# CHR_ver2.net
KiCad netlist of a schematic drawn in EAGLE
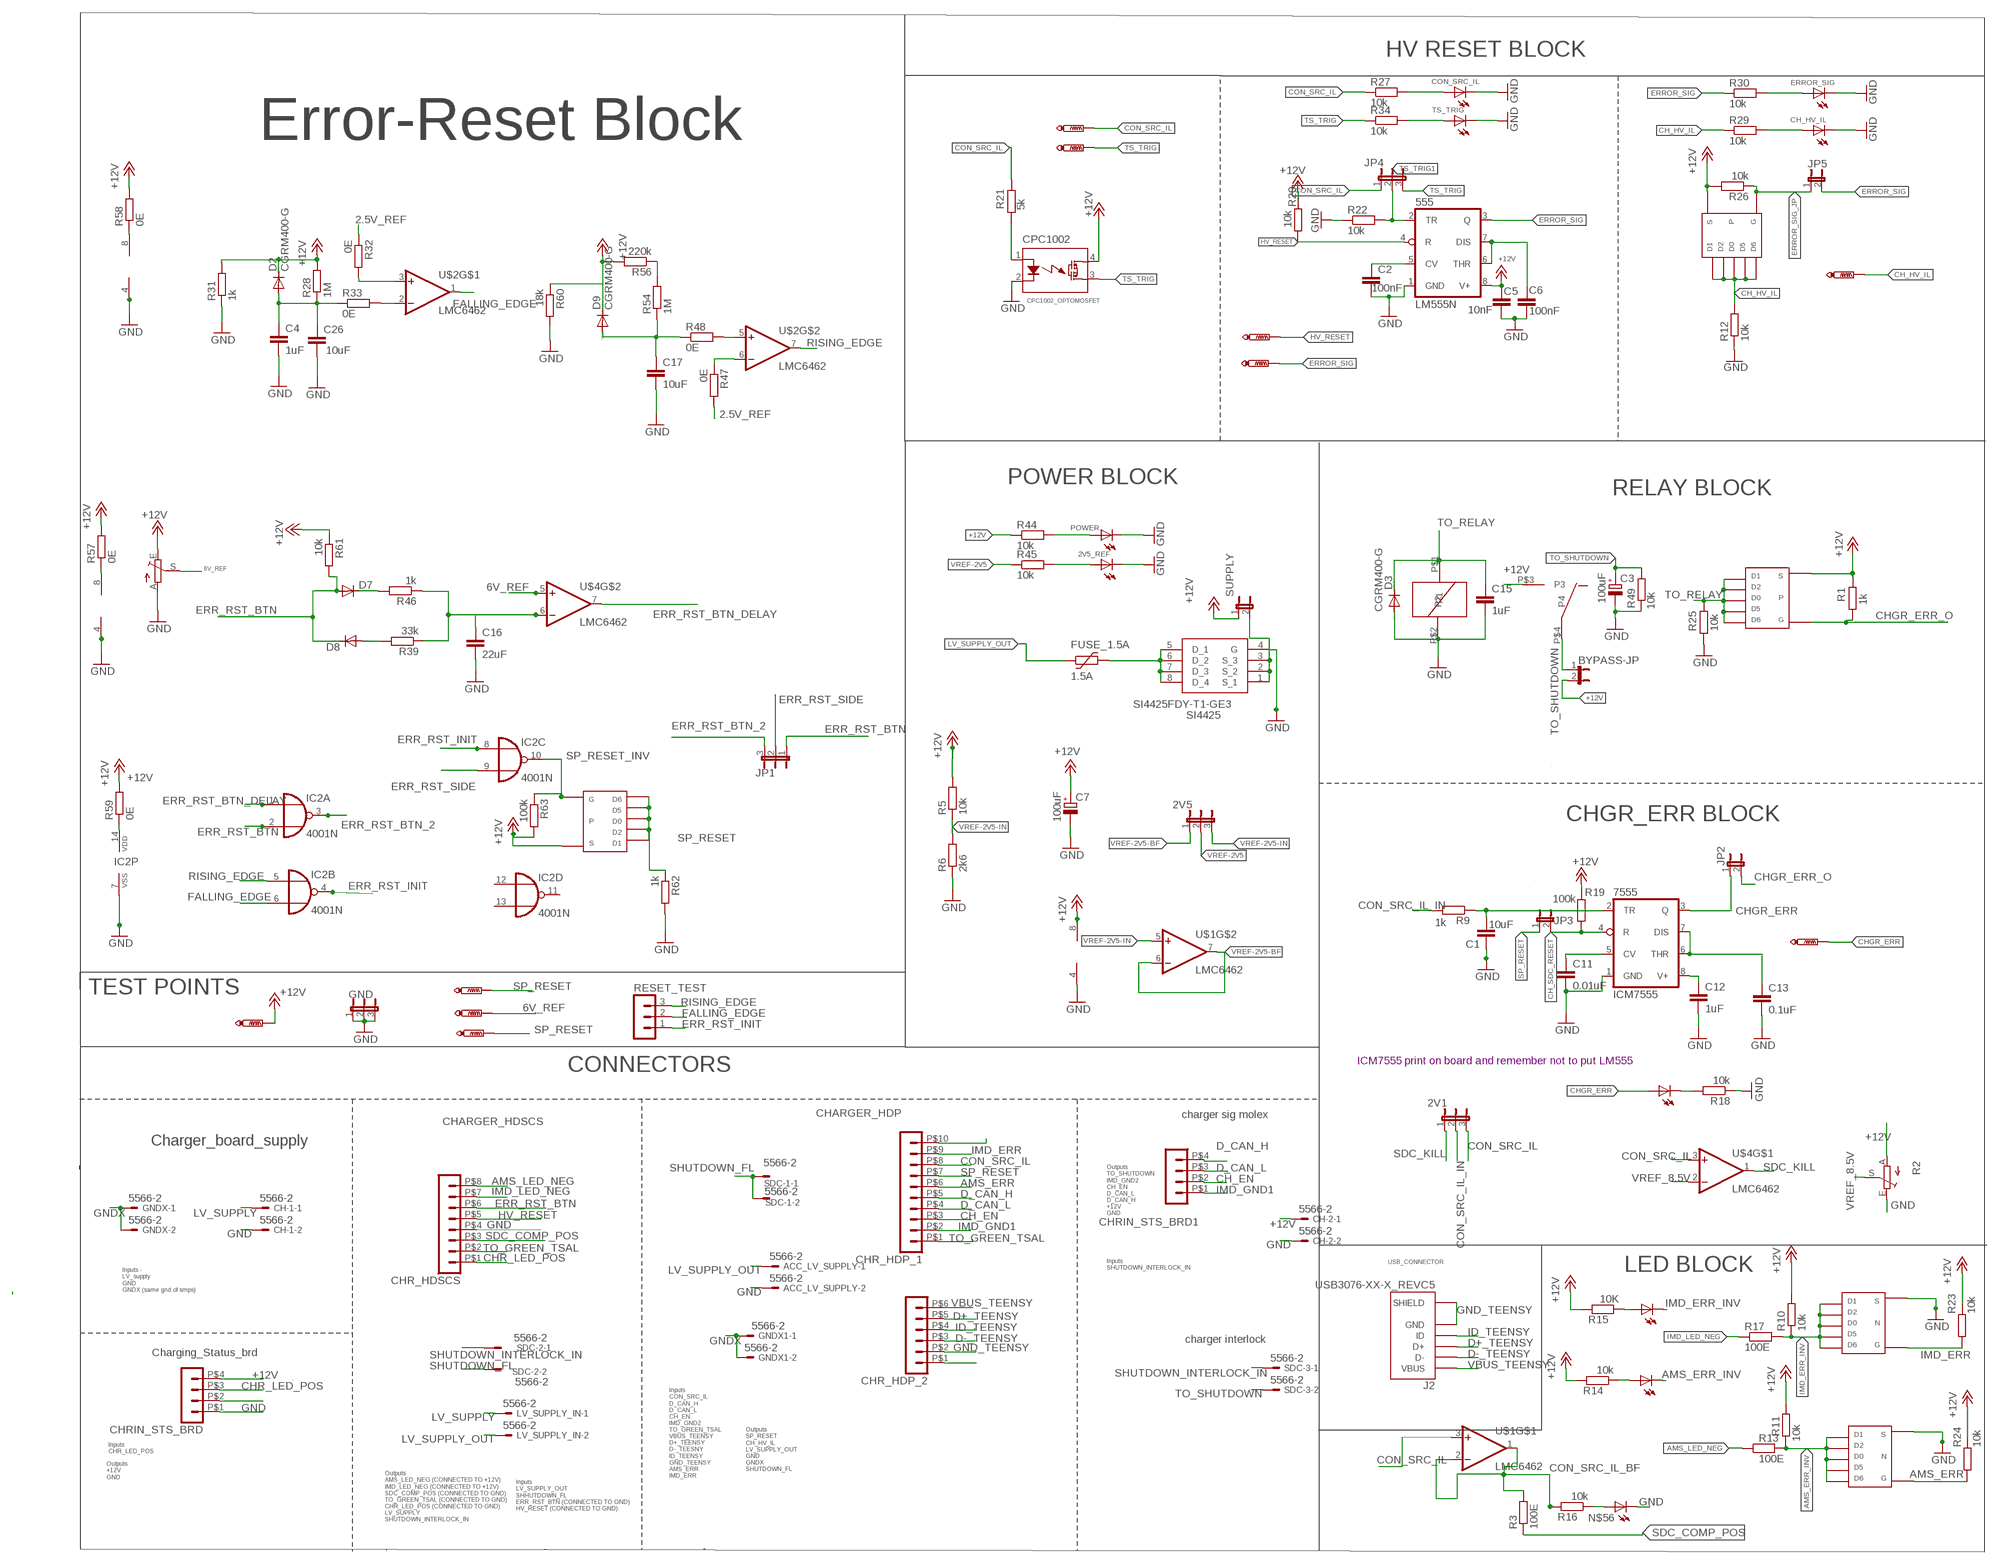
[diagram p0: schematic, sheet 1]

(export (version "E")
  (design (tool "Eeschema 10.0.6"))
  (components
    (comp (ref "+12V")
      (value "PTR1PAD1-13")
      (footprint "eagle-import:P1-13")
      (libsource (lib "eagle-import") (part "PTR1PAD1-13"))
    )
    (comp (ref "2V1")
      (value "JP2E")
      (footprint "eagle-import:JP2")
      (libsource (lib "eagle-import") (part "JP2E"))
    )
    (comp (ref "2V5")
      (value "JP2E")
      (footprint "eagle-import:JP2")
      (libsource (lib "eagle-import") (part "JP2E"))
    )
    (comp (ref "2V5_REF")
      (value "LED-FKIT-1206")
      (footprint "eagle-import:FKIT-LED-1206")
      (libsource (lib "eagle-import") (part "LED-FKIT-1206"))
    )
    (comp (ref "555")
      (value "LM555N")
      (footprint "eagle-import:DIL08")
      (libsource (lib "eagle-import") (part "555NLM"))
    )
    (comp (ref "7555")
      (value "ICM7555")
      (footprint "eagle-import:DIL08")
      (libsource (lib "eagle-import") (part "555NLM"))
    )
    (comp (ref "ACC_LV_SUPPLY")
      (value "5566-2")
      (footprint "eagle-import:5566-2")
      (fields (field (name "MF") "MOLEX"))
      (libsource (lib "eagle-import") (part "5566-2"))
    )
    (comp (ref "AMS")
      (value "LED-FKIT-1206")
      (footprint "eagle-import:FKIT-LED-1206")
      (libsource (lib "eagle-import") (part "LED-FKIT-1206"))
    )
    (comp (ref "AMS1")
      (value "LED-FKIT-1206")
      (footprint "eagle-import:FKIT-LED-1206")
      (libsource (lib "eagle-import") (part "LED-FKIT-1206"))
    )
    (comp (ref "BYPASS-JP")
      (value "JP1E")
      (footprint "eagle-import:JP1")
      (libsource (lib "eagle-import") (part "JP1E"))
    )
    (comp (ref "C1")
      (value "10uF")
      (footprint "eagle-import:C0805")
      (libsource (lib "eagle-import") (part "C-EUC0805"))
    )
    (comp (ref "C2")
      (value "100nF")
      (footprint "eagle-import:C0805")
      (libsource (lib "eagle-import") (part "C-EUC0805"))
    )
    (comp (ref "C3")
      (value "100uF")
      (footprint "eagle-import:E2,5-6")
      (libsource (lib "eagle-import") (part "CPOL-EUE2.5-6"))
    )
    (comp (ref "C4")
      (value "1uF")
      (footprint "eagle-import:C0805")
      (libsource (lib "eagle-import") (part "C-EUC0805"))
    )
    (comp (ref "C5")
      (value "10nF")
      (footprint "eagle-import:C0805")
      (libsource (lib "eagle-import") (part "C-EUC0805"))
    )
    (comp (ref "C6")
      (value "100nF")
      (footprint "eagle-import:C0805")
      (libsource (lib "eagle-import") (part "C-EUC0805"))
    )
    (comp (ref "C7")
      (value "100uF")
      (footprint "eagle-import:E2,5-6")
      (libsource (lib "eagle-import") (part "CPOL-EUE2.5-6"))
    )
    (comp (ref "C11")
      (value "0.01uF")
      (footprint "eagle-import:C0805")
      (libsource (lib "eagle-import") (part "C-EUC0805"))
    )
    (comp (ref "C12")
      (value "1uF")
      (footprint "eagle-import:C0805")
      (libsource (lib "eagle-import") (part "C-EUC0805"))
    )
    (comp (ref "C13")
      (value "0.1uF")
      (footprint "eagle-import:C0805")
      (libsource (lib "eagle-import") (part "C-EUC0805"))
    )
    (comp (ref "C15")
      (value "1uF")
      (footprint "eagle-import:C0805")
      (libsource (lib "eagle-import") (part "C-EUC0805"))
    )
    (comp (ref "C16")
      (value "22uF")
      (footprint "eagle-import:C0805")
      (libsource (lib "eagle-import") (part "C-EUC0805"))
    )
    (comp (ref "C17")
      (value "10uF")
      (footprint "eagle-import:C0805")
      (libsource (lib "eagle-import") (part "C-EUC0805"))
    )
    (comp (ref "C26")
      (value "10uF")
      (footprint "eagle-import:C0805")
      (libsource (lib "eagle-import") (part "C-EUC0805"))
    )
    (comp (ref "CH-1")
      (value "5566-2")
      (footprint "eagle-import:5566-2")
      (fields (field (name "MF") "MOLEX"))
      (libsource (lib "eagle-import") (part "5566-2"))
    )
    (comp (ref "CH-2")
      (value "5566-2")
      (footprint "eagle-import:5566-2")
      (fields (field (name "MF") "MOLEX"))
      (libsource (lib "eagle-import") (part "5566-2"))
    )
    (comp (ref "CH-HV-IL")
      (value "PTR1PAD1-13")
      (footprint "eagle-import:P1-13")
      (libsource (lib "eagle-import") (part "PTR1PAD1-13"))
    )
    (comp (ref "CHGR-ERR")
      (value "PTR1PAD1-13")
      (footprint "eagle-import:P1-13")
      (libsource (lib "eagle-import") (part "PTR1PAD1-13"))
    )
    (comp (ref "CHGR_ERR")
      (value "LED-FKIT-1206")
      (footprint "eagle-import:FKIT-LED-1206")
      (libsource (lib "eagle-import") (part "LED-FKIT-1206"))
    )
    (comp (ref "CHRIN_STS_BRD")
      (value "HEADER_POS4_44914-0401")
      (footprint "eagle-import:44914-0401")
      (libsource (lib "eagle-import") (part "HEADER_POS4_?44914-0401"))
    )
    (comp (ref "CHRIN_STS_BRD1")
      (value "HEADER_POS4_44914-0401")
      (footprint "eagle-import:44914-0401")
      (libsource (lib "eagle-import") (part "HEADER_POS4_?44914-0401"))
    )
    (comp (ref "CHR_HDP_1")
      (value "HEADER_POS10_44914-1001")
      (footprint "eagle-import:44914-1001")
      (libsource (lib "eagle-import") (part "HEADER_POS10_?44914-1001"))
    )
    (comp (ref "CHR_HDP_2")
      (value "HEADER_POS6_44914-0601")
      (footprint "eagle-import:44914-0601")
      (libsource (lib "eagle-import") (part "HEADER_POS6_?44914-0601"))
    )
    (comp (ref "CHR_HDSCS")
      (value "HEADER_POS8_44914-0801")
      (footprint "eagle-import:44914-0801")
      (libsource (lib "eagle-import") (part "HEADER_POS8_?44914-0801"))
    )
    (comp (ref "CH_HV_IL")
      (value "LED-FKIT-1206")
      (footprint "eagle-import:FKIT-LED-1206")
      (libsource (lib "eagle-import") (part "LED-FKIT-1206"))
    )
    (comp (ref "CON-SRC-IL")
      (value "PTR1PAD1-13")
      (footprint "eagle-import:P1-13")
      (libsource (lib "eagle-import") (part "PTR1PAD1-13"))
    )
    (comp (ref "CON_SRC_IL")
      (value "LED-FKIT-1206")
      (footprint "eagle-import:FKIT-LED-1206")
      (libsource (lib "eagle-import") (part "LED-FKIT-1206"))
    )
    (comp (ref "CPC1002")
      (value "CPC1002_OPTOMOSFET")
      (footprint "eagle-import:SOP04")
      (libsource (lib "eagle-import") (part "CPC1002_OPTOMOSFET"))
    )
    (comp (ref "D2")
      (value "CGRM400-G")
      (footprint "eagle-import:SOD-123_MINI-SMA")
      (libsource (lib "eagle-import") (part "CGRM400-G"))
    )
    (comp (ref "D3")
      (value "CGRM400-G")
      (footprint "eagle-import:SOD-123_MINI-SMA")
      (libsource (lib "eagle-import") (part "CGRM400-G"))
    )
    (comp (ref "D7")
      (value "DIODE-DO214AC")
      (footprint "eagle-import:DO214AC")
      (libsource (lib "eagle-import") (part "DIODE-DO214AC"))
    )
    (comp (ref "D8")
      (value "DIODE-DO214AC")
      (footprint "eagle-import:DO214AC")
      (libsource (lib "eagle-import") (part "DIODE-DO214AC"))
    )
    (comp (ref "D9")
      (value "CGRM400-G")
      (footprint "eagle-import:SOD-123_MINI-SMA")
      (libsource (lib "eagle-import") (part "CGRM400-G"))
    )
    (comp (ref "ERROR-SIG")
      (value "PTR1PAD1-13")
      (footprint "eagle-import:P1-13")
      (libsource (lib "eagle-import") (part "PTR1PAD1-13"))
    )
    (comp (ref "ERROR_SIG")
      (value "LED-FKIT-1206")
      (footprint "eagle-import:FKIT-LED-1206")
      (libsource (lib "eagle-import") (part "LED-FKIT-1206"))
    )
    (comp (ref "FUSE_1.5A")
      (value "1.5A")
      (footprint "eagle-import:1206L")
      (fields (field (name "MFR") "Littelfuse"))
      (libsource (lib "eagle-import") (part "1206L"))
    )
    (comp (ref "GND")
      (value "JP2E")
      (footprint "eagle-import:JP2")
      (libsource (lib "eagle-import") (part "JP2E"))
    )
    (comp (ref "GNDX")
      (value "5566-2")
      (footprint "eagle-import:5566-2")
      (fields (field (name "MF") "MOLEX"))
      (libsource (lib "eagle-import") (part "5566-2"))
    )
    (comp (ref "GNDX1")
      (value "5566-2")
      (footprint "eagle-import:5566-2")
      (fields (field (name "MF") "MOLEX"))
      (libsource (lib "eagle-import") (part "5566-2"))
    )
    (comp (ref "HV-RESET")
      (value "PTR1PAD1-13")
      (footprint "eagle-import:P1-13")
      (libsource (lib "eagle-import") (part "PTR1PAD1-13"))
    )
    (comp (ref "IC2")
      (value "4001N")
      (footprint "eagle-import:DIL14")
      (libsource (lib "eagle-import") (part "4001N"))
    )
    (comp (ref "IMD")
      (value "LED-FKIT-1206")
      (footprint "eagle-import:FKIT-LED-1206")
      (libsource (lib "eagle-import") (part "LED-FKIT-1206"))
    )
    (comp (ref "J2")
      (value "USB3076-XX-X_REVC5")
      (footprint "eagle-import:GCT_USB3076-XX-X_REVC5")
      (fields (field (name "MF") "Global Connector Technology") (field (name "MP") "USB3076-30-A"))
      (libsource (lib "eagle-import") (part "USB3076-XX-X_REVC5"))
    )
    (comp (ref "JP1")
      (value "JP2E")
      (footprint "eagle-import:JP2")
      (libsource (lib "eagle-import") (part "JP2E"))
    )
    (comp (ref "JP2")
      (value "JP1E")
      (footprint "eagle-import:JP1")
      (libsource (lib "eagle-import") (part "JP1E"))
    )
    (comp (ref "JP3")
      (value "JP1E")
      (footprint "eagle-import:JP1")
      (libsource (lib "eagle-import") (part "JP1E"))
    )
    (comp (ref "JP4")
      (value "JP2E")
      (footprint "eagle-import:JP2")
      (libsource (lib "eagle-import") (part "JP2E"))
    )
    (comp (ref "JP5")
      (value "JP1E")
      (footprint "eagle-import:JP1")
      (libsource (lib "eagle-import") (part "JP1E"))
    )
    (comp (ref "LV_SUPPLY_IN")
      (value "5566-2")
      (footprint "eagle-import:5566-2")
      (fields (field (name "MF") "MOLEX"))
      (libsource (lib "eagle-import") (part "5566-2"))
    )
    (comp (ref "POWER")
      (value "LED-FKIT-1206")
      (footprint "eagle-import:FKIT-LED-1206")
      (libsource (lib "eagle-import") (part "LED-FKIT-1206"))
    )
    (comp (ref "R1")
      (value "1k")
      (footprint "eagle-import:R0805")
      (libsource (lib "eagle-import") (part "R-EU_R0805"))
    )
    (comp (ref "R2")
      (value "TRIM_EU-S63S")
      (footprint "eagle-import:S63S")
      (libsource (lib "eagle-import") (part "TRIM_EU-S63S"))
    )
    (comp (ref "R3")
      (value "100E")
      (footprint "eagle-import:M0805")
      (libsource (lib "eagle-import") (part "rcl_334_R-EU_M0805"))
    )
    (comp (ref "R5")
      (value "10k")
      (footprint "eagle-import:R0805")
      (libsource (lib "eagle-import") (part "R-EU_R0805"))
    )
    (comp (ref "R6")
      (value "2k6")
      (footprint "eagle-import:R0805")
      (libsource (lib "eagle-import") (part "R-EU_R0805"))
    )
    (comp (ref "R9")
      (value "1k")
      (footprint "eagle-import:R0805")
      (libsource (lib "eagle-import") (part "R-EU_R0805"))
    )
    (comp (ref "R10")
      (value "10k")
      (footprint "eagle-import:R0805")
      (libsource (lib "eagle-import") (part "R-EU_R0805"))
    )
    (comp (ref "R11")
      (value "10k")
      (footprint "eagle-import:R0805")
      (libsource (lib "eagle-import") (part "R-EU_R0805"))
    )
    (comp (ref "R12")
      (value "10k")
      (footprint "eagle-import:R0805")
      (libsource (lib "eagle-import") (part "R-EU_R0805"))
    )
    (comp (ref "R13")
      (value "100E")
      (footprint "eagle-import:M0805")
      (libsource (lib "eagle-import") (part "rcl_334_R-EU_M0805"))
    )
    (comp (ref "R14")
      (value "10k")
      (footprint "eagle-import:M0805")
      (libsource (lib "eagle-import") (part "rcl_334_R-EU_M0805"))
    )
    (comp (ref "R15")
      (value "10K")
      (footprint "eagle-import:M0805")
      (libsource (lib "eagle-import") (part "rcl_334_R-EU_M0805"))
    )
    (comp (ref "R16")
      (value "10k")
      (footprint "eagle-import:M0805")
      (libsource (lib "eagle-import") (part "rcl_334_R-EU_M0805"))
    )
    (comp (ref "R17")
      (value "100E")
      (footprint "eagle-import:M0805")
      (libsource (lib "eagle-import") (part "rcl_334_R-EU_M0805"))
    )
    (comp (ref "R18")
      (value "10k")
      (footprint "eagle-import:R0805")
      (libsource (lib "eagle-import") (part "R-EU_R0805"))
    )
    (comp (ref "R19")
      (value "100k")
      (footprint "eagle-import:R0805")
      (libsource (lib "eagle-import") (part "R-EU_R0805"))
    )
    (comp (ref "R20")
      (value "10k")
      (footprint "eagle-import:R0805")
      (libsource (lib "eagle-import") (part "R-EU_R0805"))
    )
    (comp (ref "R21")
      (value "5k")
      (footprint "eagle-import:R0805")
      (libsource (lib "eagle-import") (part "R-EU_R0805"))
    )
    (comp (ref "R22")
      (value "10k")
      (footprint "eagle-import:R0805")
      (libsource (lib "eagle-import") (part "R-EU_R0805"))
    )
    (comp (ref "R23")
      (value "10k")
      (footprint "eagle-import:R0805")
      (libsource (lib "eagle-import") (part "R-EU_R0805"))
    )
    (comp (ref "R24")
      (value "10k")
      (footprint "eagle-import:R0805")
      (libsource (lib "eagle-import") (part "R-EU_R0805"))
    )
    (comp (ref "R25")
      (value "10k")
      (footprint "eagle-import:R0805")
      (libsource (lib "eagle-import") (part "R-EU_R0805"))
    )
    (comp (ref "R26")
      (value "10k")
      (footprint "eagle-import:R0805")
      (libsource (lib "eagle-import") (part "R-EU_R0805"))
    )
    (comp (ref "R27")
      (value "10k")
      (footprint "eagle-import:R0805")
      (libsource (lib "eagle-import") (part "R-EU_R0805"))
    )
    (comp (ref "R28")
      (value "1M")
      (footprint "eagle-import:R0805")
      (libsource (lib "eagle-import") (part "R-EU_R0805"))
    )
    (comp (ref "R29")
      (value "10k")
      (footprint "eagle-import:R0805")
      (libsource (lib "eagle-import") (part "R-EU_R0805"))
    )
    (comp (ref "R30")
      (value "10k")
      (footprint "eagle-import:R0805")
      (libsource (lib "eagle-import") (part "R-EU_R0805"))
    )
    (comp (ref "R31")
      (value "1k")
      (footprint "eagle-import:R0805")
      (libsource (lib "eagle-import") (part "R-EU_R0805"))
    )
    (comp (ref "R32")
      (value "0E")
      (footprint "eagle-import:R0805")
      (libsource (lib "eagle-import") (part "R-EU_R0805"))
    )
    (comp (ref "R33")
      (value "0E")
      (footprint "eagle-import:R0805")
      (libsource (lib "eagle-import") (part "R-EU_R0805"))
    )
    (comp (ref "R34")
      (value "10k")
      (footprint "eagle-import:R0805")
      (libsource (lib "eagle-import") (part "R-EU_R0805"))
    )
    (comp (ref "R39")
      (value "33k")
      (footprint "eagle-import:R0805")
      (libsource (lib "eagle-import") (part "R-EU_R0805"))
    )
    (comp (ref "R44")
      (value "10k")
      (footprint "eagle-import:R0805")
      (libsource (lib "eagle-import") (part "R-EU_R0805"))
    )
    (comp (ref "R45")
      (value "10k")
      (footprint "eagle-import:R0805")
      (libsource (lib "eagle-import") (part "R-EU_R0805"))
    )
    (comp (ref "R46")
      (value "1k")
      (footprint "eagle-import:R0805")
      (libsource (lib "eagle-import") (part "R-EU_R0805"))
    )
    (comp (ref "R47")
      (value "0E")
      (footprint "eagle-import:R0805")
      (libsource (lib "eagle-import") (part "R-EU_R0805"))
    )
    (comp (ref "R48")
      (value "0E")
      (footprint "eagle-import:R0805")
      (libsource (lib "eagle-import") (part "R-EU_R0805"))
    )
    (comp (ref "R49")
      (value "10k")
      (footprint "eagle-import:R0805")
      (libsource (lib "eagle-import") (part "R-EU_R0805"))
    )
    (comp (ref "R54")
      (value "1M")
      (footprint "eagle-import:R0805")
      (libsource (lib "eagle-import") (part "R-EU_R0805"))
    )
    (comp (ref "R56")
      (value "220k")
      (footprint "eagle-import:R0805")
      (libsource (lib "eagle-import") (part "R-EU_R0805"))
    )
    (comp (ref "R57")
      (value "0E")
      (footprint "eagle-import:R0805")
      (libsource (lib "eagle-import") (part "R-EU_R0805"))
    )
    (comp (ref "R58")
      (value "0E")
      (footprint "eagle-import:R0805")
      (libsource (lib "eagle-import") (part "R-EU_R0805"))
    )
    (comp (ref "R59")
      (value "0E")
      (footprint "eagle-import:R0805")
      (libsource (lib "eagle-import") (part "R-EU_R0805"))
    )
    (comp (ref "R60")
      (value "18k")
      (footprint "eagle-import:R0805")
      (libsource (lib "eagle-import") (part "R-EU_R0805"))
    )
    (comp (ref "R61")
      (value "10k")
      (footprint "eagle-import:R0805")
      (libsource (lib "eagle-import") (part "R-EU_R0805"))
    )
    (comp (ref "R62")
      (value "1k")
      (footprint "eagle-import:R0805")
      (libsource (lib "eagle-import") (part "R-EU_R0805"))
    )
    (comp (ref "R63")
      (value "100k")
      (footprint "eagle-import:R0805")
      (libsource (lib "eagle-import") (part "R-EU_R0805"))
    )
    (comp (ref "REF_POT1")
      (value "10k")
      (footprint "eagle-import:S63S")
      (libsource (lib "eagle-import") (part "TRIM_EU-S63S"))
    )
    (comp (ref "RESET_TEST")
      (value "MA03-1")
      (footprint "eagle-import:MA03-1")
      (libsource (lib "eagle-import") (part "MA03-1"))
    )
    (comp (ref "SDC-1")
      (value "5566-2")
      (footprint "eagle-import:5566-2")
      (fields (field (name "MF") "MOLEX"))
      (libsource (lib "eagle-import") (part "5566-2"))
    )
    (comp (ref "SDC-2")
      (value "5566-2")
      (footprint "eagle-import:5566-2")
      (fields (field (name "MF") "MOLEX"))
      (libsource (lib "eagle-import") (part "5566-2"))
    )
    (comp (ref "SDC-3")
      (value "5566-2")
      (footprint "eagle-import:5566-2")
      (fields (field (name "MF") "MOLEX"))
      (libsource (lib "eagle-import") (part "5566-2"))
    )
    (comp (ref "SI4425")
      (value "SI4425FDY-T1-GE3")
      (footprint "eagle-import:SOIC127P600X175-8N")
      (fields (field (name "MOUSER_PART_NUMBER") "78-SI4425FDY-T1-GE3"))
      (libsource (lib "eagle-import") (part "SI4425FDY-T1-GE3"))
    )
    (comp (ref "SP_RESET")
      (value "PTR1PAD1-13")
      (footprint "eagle-import:P1-13")
      (libsource (lib "eagle-import") (part "PTR1PAD1-13"))
    )
    (comp (ref "SP_RESET1")
      (value "PTR1PAD1-13")
      (footprint "eagle-import:P1-13")
      (libsource (lib "eagle-import") (part "PTR1PAD1-13"))
    )
    (comp (ref "SP_RESET2")
      (value "PTR1PAD1-13")
      (footprint "eagle-import:P1-13")
      (libsource (lib "eagle-import") (part "PTR1PAD1-13"))
    )
    (comp (ref "SUPPLY")
      (value "JP1E")
      (footprint "eagle-import:JP1")
      (libsource (lib "eagle-import") (part "JP1E"))
    )
    (comp (ref "TS-TRIG")
      (value "PTR1PAD1-13")
      (footprint "eagle-import:P1-13")
      (libsource (lib "eagle-import") (part "PTR1PAD1-13"))
    )
    (comp (ref "TS_TRIG")
      (value "LED-FKIT-1206")
      (footprint "eagle-import:FKIT-LED-1206")
      (libsource (lib "eagle-import") (part "LED-FKIT-1206"))
    )
    (comp (ref "U$1")
      (value "LMC6462")
      (footprint "eagle-import:S08")
      (libsource (lib "eagle-import") (part "LMC6462"))
    )
    (comp (ref "U$2")
      (value "LMC6462")
      (footprint "eagle-import:S08")
      (libsource (lib "eagle-import") (part "LMC6462"))
    )
    (comp (ref "U$3")
      (value "TSOP-6_PMOS")
      (footprint "eagle-import:TSOP-6_PMOS")
      (libsource (lib "eagle-import") (part "TSOP-6_MOS_TSOP-6_PMOS"))
    )
    (comp (ref "U$4")
      (value "LMC6462")
      (footprint "eagle-import:S08")
      (libsource (lib "eagle-import") (part "LMC6462"))
    )
    (comp (ref "U$5")
      (value "TSOP-6_NMOS")
      (footprint "eagle-import:TSOP-6_NMOS")
      (libsource (lib "eagle-import") (part "TSOP-6_NMOS"))
    )
    (comp (ref "U$7")
      (value "TSOP-6_NMOS")
      (footprint "eagle-import:TSOP-6_NMOS")
      (libsource (lib "eagle-import") (part "TSOP-6_NMOS"))
    )
    (comp (ref "U$8")
      (value "TSOP-6_PMOS")
      (footprint "eagle-import:TSOP-6_PMOS")
      (libsource (lib "eagle-import") (part "TSOP-6_PMOS"))
    )
    (comp (ref "U$9")
      (value "G6DN_RELAY")
      (footprint "eagle-import:G6DN_RELAY")
      (libsource (lib "eagle-import") (part "G6DN_RELAY"))
    )
    (comp (ref "U$11")
      (value "TSOP-6_PMOS")
      (footprint "eagle-import:TSOP-6_PMOS")
      (libsource (lib "eagle-import") (part "TSOP-6_MOS_TSOP-6_PMOS"))
    )
  )
  (nets
    (net (code "1") (name "+12V") (class "Default")
      (node (ref "+12V") (pin "TP") (pinfunction "TP_TP") (pintype "input"))
      (node (ref "555") (pin "8") (pinfunction "V+_8") (pintype "power_in"))
      (node (ref "7555") (pin "8") (pinfunction "V+_8") (pintype "power_in"))
      (node (ref "BYPASS-JP") (pin "2") (pinfunction "2_2") (pintype "passive"))
      (node (ref "C12") (pin "1") (pinfunction "1_1") (pintype "passive"))
      (node (ref "C5") (pin "1") (pinfunction "1_1") (pintype "passive"))
      (node (ref "C7") (pin "+") (pinfunction "+_+") (pintype "passive"))
      (node (ref "CH-2") (pin "1") (pinfunction "S_1") (pintype "passive"))
      (node (ref "CHRIN_STS_BRD") (pin "P$4") (pinfunction "4_P$4") (pintype "passive"))
      (node (ref "CPC1002") (pin "4") (pinfunction "4_4") (pintype "passive"))
      (node (ref "D2") (pin "C") (pinfunction "C_C") (pintype "passive"))
      (node (ref "D9") (pin "C") (pinfunction "C_C") (pintype "passive"))
      (node (ref "R1") (pin "2") (pinfunction "2_2") (pintype "passive"))
      (node (ref "R10") (pin "2") (pinfunction "2_2") (pintype "passive"))
      (node (ref "R11") (pin "2") (pinfunction "2_2") (pintype "passive"))
      (node (ref "R14") (pin "2") (pinfunction "2_2") (pintype "passive"))
      (node (ref "R15") (pin "2") (pinfunction "2_2") (pintype "passive"))
      (node (ref "R19") (pin "1") (pinfunction "1_1") (pintype "passive"))
      (node (ref "R2") (pin "A") (pinfunction "A_A") (pintype "passive"))
      (node (ref "R20") (pin "2") (pinfunction "2_2") (pintype "passive"))
      (node (ref "R23") (pin "2") (pinfunction "2_2") (pintype "passive"))
      (node (ref "R24") (pin "2") (pinfunction "2_2") (pintype "passive"))
      (node (ref "R26") (pin "2") (pinfunction "2_2") (pintype "passive"))
      (node (ref "R28") (pin "2") (pinfunction "2_2") (pintype "passive"))
      (node (ref "R31") (pin "2") (pinfunction "2_2") (pintype "passive"))
      (node (ref "R44") (pin "1") (pinfunction "1_1") (pintype "passive"))
      (node (ref "R5") (pin "2") (pinfunction "2_2") (pintype "passive"))
      (node (ref "R56") (pin "2") (pinfunction "2_2") (pintype "passive"))
      (node (ref "R57") (pin "2") (pinfunction "2_2") (pintype "passive"))
      (node (ref "R58") (pin "2") (pinfunction "2_2") (pintype "passive"))
      (node (ref "R59") (pin "2") (pinfunction "2_2") (pintype "passive"))
      (node (ref "R60") (pin "1") (pinfunction "1_1") (pintype "passive"))
      (node (ref "R61") (pin "1") (pinfunction "1_1") (pintype "passive"))
      (node (ref "R63") (pin "2") (pinfunction "2_2") (pintype "passive"))
      (node (ref "REF_POT1") (pin "E") (pinfunction "E_E") (pintype "passive"))
      (node (ref "SUPPLY") (pin "1") (pinfunction "1_1") (pintype "passive"))
      (node (ref "U$1") (pin "8") (pinfunction "V+_8") (pintype "power_in"))
      (node (ref "U$11") (pin "S") (pinfunction "S_S") (pintype "bidirectional"))
      (node (ref "U$3") (pin "S") (pinfunction "S_S") (pintype "bidirectional"))
      (node (ref "U$8") (pin "S") (pinfunction "S_S") (pintype "bidirectional"))
      (node (ref "U$9") (pin "P$3") (pinfunction "P3_P$3") (pintype "bidirectional"))
    )
    (net (code "2") (name "2.5V_REF") (class "Default")
      (node (ref "R32") (pin "1") (pinfunction "1_1") (pintype "passive"))
      (node (ref "R47") (pin "2") (pinfunction "2_2") (pintype "passive"))
    )
    (net (code "3") (name "6V_REF") (class "Default")
      (node (ref "REF_POT1") (pin "S") (pinfunction "S_S") (pintype "passive"))
      (node (ref "SP_RESET1") (pin "TP") (pinfunction "TP_TP") (pintype "input"))
      (node (ref "U$4") (pin "5") (pinfunction "+IN_5") (pintype "input"))
    )
    (net (code "4") (name "AMS_ERR") (class "Default")
      (node (ref "CHR_HDP_1") (pin "P$6") (pinfunction "6_P$6") (pintype "passive"))
      (node (ref "R24") (pin "1") (pinfunction "1_1") (pintype "passive"))
      (node (ref "U$5") (pin "G") (pinfunction "G_G") (pintype "bidirectional"))
    )
    (net (code "5") (name "AMS_ERR_INV") (class "Default")
      (node (ref "AMS") (pin "C") (pinfunction "C_C") (pintype "passive"))
      (node (ref "R11") (pin "1") (pinfunction "1_1") (pintype "passive"))
      (node (ref "R13") (pin "2") (pinfunction "2_2") (pintype "passive"))
      (node (ref "U$5") (pin "1") (pinfunction "1_1") (pintype "bidirectional"))
      (node (ref "U$5") (pin "2") (pinfunction "2_2") (pintype "bidirectional"))
      (node (ref "U$5") (pin "5") (pinfunction "5_5") (pintype "bidirectional"))
      (node (ref "U$5") (pin "6") (pinfunction "6_6") (pintype "bidirectional"))
      (node (ref "U$5") (pin "D") (pinfunction "D0_D") (pintype "bidirectional"))
    )
    (net (code "6") (name "AMS_LED_NEG") (class "Default")
      (node (ref "CHR_HDSCS") (pin "P$8") (pinfunction "8_P$8") (pintype "passive"))
      (node (ref "R13") (pin "1") (pinfunction "1_1") (pintype "passive"))
    )
    (net (code "7") (name "CHGR_ERR") (class "Default")
      (node (ref "7555") (pin "3") (pinfunction "Q_3") (pintype "output"))
      (node (ref "CHGR-ERR") (pin "TP") (pinfunction "TP_TP") (pintype "input"))
      (node (ref "CHGR_ERR") (pin "A") (pinfunction "A_A") (pintype "passive"))
      (node (ref "JP2") (pin "1") (pinfunction "1_1") (pintype "passive"))
    )
    (net (code "8") (name "CHGR_ERR_O") (class "Default")
      (node (ref "JP2") (pin "2") (pinfunction "2_2") (pintype "passive"))
      (node (ref "R1") (pin "1") (pinfunction "1_1") (pintype "passive"))
      (node (ref "U$3") (pin "G") (pinfunction "G_G") (pintype "bidirectional"))
    )
    (net (code "9") (name "CHR_LED_POS") (class "Default")
      (node (ref "CHRIN_STS_BRD") (pin "P$3") (pinfunction "3_P$3") (pintype "passive"))
      (node (ref "CHR_HDSCS") (pin "P$1") (pinfunction "1_P$1") (pintype "passive"))
    )
    (net (code "10") (name "CH_EN") (class "Default")
      (node (ref "CHRIN_STS_BRD1") (pin "P$2") (pinfunction "2_P$2") (pintype "passive"))
      (node (ref "CHR_HDP_1") (pin "P$3") (pinfunction "3_P$3") (pintype "passive"))
    )
    (net (code "11") (name "CH_HV_IL") (class "Default")
      (node (ref "CH-HV-IL") (pin "TP") (pinfunction "TP_TP") (pintype "input"))
      (node (ref "CHR_HDP_1") (pin "P$10") (pinfunction "10_P$10") (pintype "passive"))
      (node (ref "R12") (pin "2") (pinfunction "2_2") (pintype "passive"))
      (node (ref "R29") (pin "1") (pinfunction "1_1") (pintype "passive"))
      (node (ref "U$8") (pin "1") (pinfunction "1_1") (pintype "bidirectional"))
      (node (ref "U$8") (pin "2") (pinfunction "2_2") (pintype "bidirectional"))
      (node (ref "U$8") (pin "5") (pinfunction "5_5") (pintype "bidirectional"))
      (node (ref "U$8") (pin "6") (pinfunction "6_6") (pintype "bidirectional"))
      (node (ref "U$8") (pin "D") (pinfunction "D0_D") (pintype "bidirectional"))
    )
    (net (code "12") (name "CH_SDC_RESET") (class "Default")
      (node (ref "7555") (pin "4") (pinfunction "R_4") (pintype "input"))
      (node (ref "JP3") (pin "2") (pinfunction "2_2") (pintype "passive"))
      (node (ref "R19") (pin "2") (pinfunction "2_2") (pintype "passive"))
    )
    (net (code "13") (name "CON_SRC_IL") (class "Default")
      (node (ref "2V1") (pin "3") (pinfunction "3_3") (pintype "passive"))
      (node (ref "CHR_HDP_1") (pin "P$8") (pinfunction "8_P$8") (pintype "passive"))
      (node (ref "CON-SRC-IL") (pin "TP") (pinfunction "TP_TP") (pintype "input"))
      (node (ref "JP4") (pin "1") (pinfunction "1_1") (pintype "passive"))
      (node (ref "R21") (pin "2") (pinfunction "2_2") (pintype "passive"))
      (node (ref "R27") (pin "1") (pinfunction "1_1") (pintype "passive"))
      (node (ref "U$1") (pin "3") (pinfunction "+IN_3") (pintype "input"))
      (node (ref "U$4") (pin "3") (pinfunction "+IN_3") (pintype "input"))
    )
    (net (code "14") (name "CON_SRC_IL_BF") (class "Default")
      (node (ref "R16") (pin "2") (pinfunction "2_2") (pintype "passive"))
      (node (ref "R3") (pin "2") (pinfunction "2_2") (pintype "passive"))
      (node (ref "U$1") (pin "1") (pinfunction "OUT_1") (pintype "output"))
      (node (ref "U$1") (pin "2") (pinfunction "-IN_2") (pintype "input"))
    )
    (net (code "15") (name "CON_SRC_IL_IN") (class "Default")
      (node (ref "2V1") (pin "2") (pinfunction "2_2") (pintype "passive"))
      (node (ref "R9") (pin "2") (pinfunction "2_2") (pintype "passive"))
    )
    (net (code "16") (name "D+_TEENSY") (class "Default")
      (node (ref "CHR_HDP_2") (pin "P$5") (pinfunction "5_P$5") (pintype "passive"))
      (node (ref "J2") (pin "3") (pinfunction "D+_3") (pintype "bidirectional"))
    )
    (net (code "17") (name "D-_TEENSY") (class "Default")
      (node (ref "CHR_HDP_2") (pin "P$3") (pinfunction "3_P$3") (pintype "passive"))
      (node (ref "J2") (pin "2") (pinfunction "D-_2") (pintype "bidirectional"))
    )
    (net (code "18") (name "D_CAN_H") (class "Default")
      (node (ref "CHRIN_STS_BRD1") (pin "P$4") (pinfunction "4_P$4") (pintype "passive"))
      (node (ref "CHR_HDP_1") (pin "P$5") (pinfunction "5_P$5") (pintype "passive"))
    )
    (net (code "19") (name "D_CAN_L") (class "Default")
      (node (ref "CHRIN_STS_BRD1") (pin "P$3") (pinfunction "3_P$3") (pintype "passive"))
      (node (ref "CHR_HDP_1") (pin "P$4") (pinfunction "4_P$4") (pintype "passive"))
    )
    (net (code "20") (name "ERROR_SIG") (class "Default")
      (node (ref "555") (pin "3") (pinfunction "Q_3") (pintype "output"))
      (node (ref "ERROR-SIG") (pin "TP") (pinfunction "TP_TP") (pintype "input"))
      (node (ref "JP5") (pin "2") (pinfunction "2_2") (pintype "passive"))
      (node (ref "R30") (pin "1") (pinfunction "1_1") (pintype "passive"))
    )
    (net (code "21") (name "ERROR_SIG_JP") (class "Default")
      (node (ref "JP5") (pin "1") (pinfunction "1_1") (pintype "passive"))
      (node (ref "R26") (pin "1") (pinfunction "1_1") (pintype "passive"))
      (node (ref "U$8") (pin "G") (pinfunction "G_G") (pintype "bidirectional"))
    )
    (net (code "22") (name "ERR_RST_BTN") (class "Default")
      (node (ref "CHR_HDSCS") (pin "P$6") (pinfunction "6_P$6") (pintype "passive"))
      (node (ref "D7") (pin "A") (pinfunction "A_A") (pintype "passive"))
      (node (ref "D8") (pin "C") (pinfunction "C_C") (pintype "passive"))
      (node (ref "IC2") (pin "2") (pinfunction "I1_2") (pintype "input"))
      (node (ref "JP1") (pin "1") (pinfunction "1_1") (pintype "passive"))
      (node (ref "R61") (pin "2") (pinfunction "2_2") (pintype "passive"))
    )
    (net (code "23") (name "ERR_RST_BTN_2") (class "Default")
      (node (ref "IC2") (pin "3") (pinfunction "O_3") (pintype "output"))
      (node (ref "JP1") (pin "3") (pinfunction "3_3") (pintype "passive"))
    )
    (net (code "24") (name "ERR_RST_BTN_DELAY") (class "Default")
      (node (ref "IC2") (pin "1") (pinfunction "I0_1") (pintype "input"))
      (node (ref "U$4") (pin "7") (pinfunction "OUT_7") (pintype "output"))
    )
    (net (code "25") (name "ERR_RST_INIT") (class "Default")
      (node (ref "IC2") (pin "4") (pinfunction "O_4") (pintype "output"))
      (node (ref "IC2") (pin "8") (pinfunction "I0_8") (pintype "input"))
      (node (ref "RESET_TEST") (pin "1") (pinfunction "1_1") (pintype "passive"))
    )
    (net (code "26") (name "ERR_RST_SIDE") (class "Default")
      (node (ref "IC2") (pin "9") (pinfunction "I1_9") (pintype "input"))
      (node (ref "JP1") (pin "2") (pinfunction "2_2") (pintype "passive"))
    )
    (net (code "27") (name "FALLING_EDGE") (class "Default")
      (node (ref "IC2") (pin "6") (pinfunction "I1_6") (pintype "input"))
      (node (ref "RESET_TEST") (pin "2") (pinfunction "2_2") (pintype "passive"))
      (node (ref "U$2") (pin "1") (pinfunction "OUT_1") (pintype "output"))
    )
    (net (code "28") (name "GND") (class "Default")
      (node (ref "2V5_REF") (pin "C") (pinfunction "C_C") (pintype "passive"))
      (node (ref "555") (pin "1") (pinfunction "GND_1") (pintype "power_in"))
      (node (ref "7555") (pin "1") (pinfunction "GND_1") (pintype "power_in"))
      (node (ref "ACC_LV_SUPPLY") (pin "2") (pinfunction "S_2") (pintype "passive"))
      (node (ref "AMS1") (pin "C") (pinfunction "C_C") (pintype "passive"))
      (node (ref "C1") (pin "1") (pinfunction "1_1") (pintype "passive"))
      (node (ref "C11") (pin "2") (pinfunction "2_2") (pintype "passive"))
      (node (ref "C12") (pin "2") (pinfunction "2_2") (pintype "passive"))
      (node (ref "C13") (pin "2") (pinfunction "2_2") (pintype "passive"))
      (node (ref "C15") (pin "2") (pinfunction "2_2") (pintype "passive"))
      (node (ref "C16") (pin "2") (pinfunction "2_2") (pintype "passive"))
      (node (ref "C17") (pin "2") (pinfunction "2_2") (pintype "passive"))
      (node (ref "C2") (pin "2") (pinfunction "2_2") (pintype "passive"))
      (node (ref "C26") (pin "2") (pinfunction "2_2") (pintype "passive"))
      (node (ref "C3") (pin "-") (pinfunction "-_-") (pintype "passive"))
      (node (ref "C4") (pin "2") (pinfunction "2_2") (pintype "passive"))
      (node (ref "C5") (pin "2") (pinfunction "2_2") (pintype "passive"))
      (node (ref "C6") (pin "2") (pinfunction "2_2") (pintype "passive"))
      (node (ref "C7") (pin "-") (pinfunction "-_-") (pintype "passive"))
      (node (ref "CH-1") (pin "2") (pinfunction "S_2") (pintype "passive"))
      (node (ref "CH-2") (pin "2") (pinfunction "S_2") (pintype "passive"))
      (node (ref "CHRIN_STS_BRD") (pin "P$1") (pinfunction "1_P$1") (pintype "passive"))
      (node (ref "CHR_HDSCS") (pin "P$4") (pinfunction "4_P$4") (pintype "passive"))
      (node (ref "CH_HV_IL") (pin "C") (pinfunction "C_C") (pintype "passive"))
      (node (ref "CON_SRC_IL") (pin "C") (pinfunction "C_C") (pintype "passive"))
      (node (ref "CPC1002") (pin "2") (pinfunction "2_2") (pintype "passive"))
      (node (ref "D3") (pin "A") (pinfunction "A_A") (pintype "passive"))
      (node (ref "ERROR_SIG") (pin "C") (pinfunction "C_C") (pintype "passive"))
      (node (ref "GND") (pin "1") (pinfunction "1_1") (pintype "passive"))
      (node (ref "GND") (pin "2") (pinfunction "2_2") (pintype "passive"))
      (node (ref "GND") (pin "3") (pinfunction "3_3") (pintype "passive"))
      (node (ref "IC2") (pin "7") (pinfunction "VSS_7") (pintype "power_in"))
      (node (ref "POWER") (pin "C") (pinfunction "C_C") (pintype "passive"))
      (node (ref "R12") (pin "1") (pinfunction "1_1") (pintype "passive"))
      (node (ref "R18") (pin "1") (pinfunction "1_1") (pintype "passive"))
      (node (ref "R2") (pin "E") (pinfunction "E_E") (pintype "passive"))
      (node (ref "R22") (pin "1") (pinfunction "1_1") (pintype "passive"))
      (node (ref "R25") (pin "1") (pinfunction "1_1") (pintype "passive"))
      (node (ref "R31") (pin "1") (pinfunction "1_1") (pintype "passive"))
      (node (ref "R49") (pin "1") (pinfunction "1_1") (pintype "passive"))
      (node (ref "R6") (pin "1") (pinfunction "1_1") (pintype "passive"))
      (node (ref "R60") (pin "2") (pinfunction "2_2") (pintype "passive"))
      (node (ref "R62") (pin "2") (pinfunction "2_2") (pintype "passive"))
      (node (ref "REF_POT1") (pin "A") (pinfunction "A_A") (pintype "passive"))
      (node (ref "SI4425") (pin "4") (pinfunction "G_4") (pintype "bidirectional"))
      (node (ref "TS_TRIG") (pin "C") (pinfunction "C_C") (pintype "passive"))
      (node (ref "U$1") (pin "4") (pinfunction "V-_4") (pintype "power_in"))
      (node (ref "U$2") (pin "4") (pinfunction "V-_4") (pintype "power_in"))
      (node (ref "U$4") (pin "4") (pinfunction "V-_4") (pintype "power_in"))
      (node (ref "U$5") (pin "S") (pinfunction "S_S") (pintype "bidirectional"))
      (node (ref "U$7") (pin "S") (pinfunction "S_S") (pintype "bidirectional"))
      (node (ref "U$9") (pin "P$2") (pinfunction "P2_P$2") (pintype "bidirectional"))
    )
    (net (code "29") (name "GNDX") (class "Default")
      (node (ref "GNDX") (pin "1") (pinfunction "S_1") (pintype "passive"))
      (node (ref "GNDX") (pin "2") (pinfunction "S_2") (pintype "passive"))
      (node (ref "GNDX1") (pin "1") (pinfunction "S_1") (pintype "passive"))
      (node (ref "GNDX1") (pin "2") (pinfunction "S_2") (pintype "passive"))
    )
    (net (code "30") (name "GND_TEENSY") (class "Default")
      (node (ref "CHR_HDP_2") (pin "P$2") (pinfunction "2_P$2") (pintype "passive"))
      (node (ref "J2") (pin "10") (pinfunction "SHIELD_10") (pintype "power_in"))
      (node (ref "J2") (pin "11") (pinfunction "SHIELD_11") (pintype "power_in"))
      (node (ref "J2") (pin "5") (pinfunction "GND_5") (pintype "power_in"))
      (node (ref "J2") (pin "6") (pinfunction "SHIELD_6") (pintype "power_in"))
      (node (ref "J2") (pin "7") (pinfunction "SHIELD_7") (pintype "power_in"))
      (node (ref "J2") (pin "8") (pinfunction "SHIELD_8") (pintype "power_in"))
      (node (ref "J2") (pin "9") (pinfunction "SHIELD_9") (pintype "power_in"))
    )
    (net (code "31") (name "HV_RESET") (class "Default")
      (node (ref "555") (pin "4") (pinfunction "R_4") (pintype "input"))
      (node (ref "CHR_HDSCS") (pin "P$5") (pinfunction "5_P$5") (pintype "passive"))
      (node (ref "HV-RESET") (pin "TP") (pinfunction "TP_TP") (pintype "input"))
      (node (ref "R20") (pin "1") (pinfunction "1_1") (pintype "passive"))
    )
    (net (code "32") (name "ID_TEENSY") (class "Default")
      (node (ref "CHR_HDP_2") (pin "P$4") (pinfunction "4_P$4") (pintype "passive"))
      (node (ref "J2") (pin "4") (pinfunction "ID_4") (pintype "bidirectional"))
    )
    (net (code "33") (name "IMD_ERR") (class "Default")
      (node (ref "CHR_HDP_1") (pin "P$9") (pinfunction "9_P$9") (pintype "passive"))
      (node (ref "R23") (pin "1") (pinfunction "1_1") (pintype "passive"))
      (node (ref "U$7") (pin "G") (pinfunction "G_G") (pintype "bidirectional"))
    )
    (net (code "34") (name "IMD_ERR_INV") (class "Default")
      (node (ref "IMD") (pin "C") (pinfunction "C_C") (pintype "passive"))
      (node (ref "R10") (pin "1") (pinfunction "1_1") (pintype "passive"))
      (node (ref "R17") (pin "2") (pinfunction "2_2") (pintype "passive"))
      (node (ref "U$7") (pin "1") (pinfunction "1_1") (pintype "bidirectional"))
      (node (ref "U$7") (pin "2") (pinfunction "2_2") (pintype "bidirectional"))
      (node (ref "U$7") (pin "5") (pinfunction "5_5") (pintype "bidirectional"))
      (node (ref "U$7") (pin "6") (pinfunction "6_6") (pintype "bidirectional"))
      (node (ref "U$7") (pin "D") (pinfunction "D0_D") (pintype "bidirectional"))
    )
    (net (code "35") (name "IMD_GND1") (class "Default")
      (node (ref "CHRIN_STS_BRD1") (pin "P$1") (pinfunction "1_P$1") (pintype "passive"))
      (node (ref "CHR_HDP_1") (pin "P$2") (pinfunction "2_P$2") (pintype "passive"))
    )
    (net (code "36") (name "IMD_LED_NEG") (class "Default")
      (node (ref "CHR_HDSCS") (pin "P$7") (pinfunction "7_P$7") (pintype "passive"))
      (node (ref "R17") (pin "1") (pinfunction "1_1") (pintype "passive"))
    )
    (net (code "37") (name "LV_SUPPLY") (class "Default")
      (node (ref "CH-1") (pin "1") (pinfunction "S_1") (pintype "passive"))
      (node (ref "LV_SUPPLY_IN") (pin "1") (pinfunction "S_1") (pintype "passive"))
    )
    (net (code "38") (name "LV_SUPPLY_OUT") (class "Default")
      (node (ref "ACC_LV_SUPPLY") (pin "1") (pinfunction "S_1") (pintype "passive"))
      (node (ref "FUSE_1.5A") (pin "P$1") (pinfunction "1_P$1") (pintype "passive"))
      (node (ref "LV_SUPPLY_IN") (pin "2") (pinfunction "S_2") (pintype "passive"))
    )
    (net (code "39") (name "N$56") (class "Default")
      (node (ref "AMS1") (pin "A") (pinfunction "A_A") (pintype "passive"))
      (node (ref "R16") (pin "1") (pinfunction "1_1") (pintype "passive"))
    )
    (net (code "40") (name "Net-(2V5_REF-PadA)") (class "Default")
      (node (ref "2V5_REF") (pin "A") (pinfunction "A_A") (pintype "passive"))
      (node (ref "R45") (pin "2") (pinfunction "2_2") (pintype "passive"))
    )
    (net (code "41") (name "Net-(555-CV)") (class "Default")
      (node (ref "555") (pin "5") (pinfunction "CV_5") (pintype "input"))
      (node (ref "C2") (pin "1") (pinfunction "1_1") (pintype "passive"))
    )
    (net (code "42") (name "Net-(555-DIS)") (class "Default")
      (node (ref "555") (pin "6") (pinfunction "THR_6") (pintype "input"))
      (node (ref "555") (pin "7") (pinfunction "DIS_7") (pintype "input"))
      (node (ref "C6") (pin "1") (pinfunction "1_1") (pintype "passive"))
    )
    (net (code "43") (name "Net-(7555-CV)") (class "Default")
      (node (ref "7555") (pin "5") (pinfunction "CV_5") (pintype "input"))
      (node (ref "C11") (pin "1") (pinfunction "1_1") (pintype "passive"))
    )
    (net (code "44") (name "Net-(7555-DIS)") (class "Default")
      (node (ref "7555") (pin "6") (pinfunction "THR_6") (pintype "input"))
      (node (ref "7555") (pin "7") (pinfunction "DIS_7") (pintype "input"))
      (node (ref "C13") (pin "1") (pinfunction "1_1") (pintype "passive"))
    )
    (net (code "45") (name "Net-(7555-TR)") (class "Default")
      (node (ref "7555") (pin "2") (pinfunction "TR_2") (pintype "input"))
      (node (ref "C1") (pin "2") (pinfunction "2_2") (pintype "passive"))
      (node (ref "R9") (pin "1") (pinfunction "1_1") (pintype "passive"))
    )
    (net (code "46") (name "Net-(AMS-PadA)") (class "Default")
      (node (ref "AMS") (pin "A") (pinfunction "A_A") (pintype "passive"))
      (node (ref "R14") (pin "1") (pinfunction "1_1") (pintype "passive"))
    )
    (net (code "47") (name "Net-(C17-Pad1)") (class "Default")
      (node (ref "C17") (pin "1") (pinfunction "1_1") (pintype "passive"))
      (node (ref "D9") (pin "A") (pinfunction "A_A") (pintype "passive"))
      (node (ref "R48") (pin "1") (pinfunction "1_1") (pintype "passive"))
      (node (ref "R54") (pin "1") (pinfunction "1_1") (pintype "passive"))
    )
    (net (code "48") (name "Net-(C26-Pad1)") (class "Default")
      (node (ref "C26") (pin "1") (pinfunction "1_1") (pintype "passive"))
      (node (ref "C4") (pin "1") (pinfunction "1_1") (pintype "passive"))
      (node (ref "D2") (pin "A") (pinfunction "A_A") (pintype "passive"))
      (node (ref "R28") (pin "1") (pinfunction "1_1") (pintype "passive"))
      (node (ref "R33") (pin "1") (pinfunction "1_1") (pintype "passive"))
    )
    (net (code "49") (name "Net-(CHGR_ERR-PadC)") (class "Default")
      (node (ref "CHGR_ERR") (pin "C") (pinfunction "C_C") (pintype "passive"))
      (node (ref "R18") (pin "2") (pinfunction "2_2") (pintype "passive"))
    )
    (net (code "50") (name "Net-(CH_HV_IL-PadA)") (class "Default")
      (node (ref "CH_HV_IL") (pin "A") (pinfunction "A_A") (pintype "passive"))
      (node (ref "R29") (pin "2") (pinfunction "2_2") (pintype "passive"))
    )
    (net (code "51") (name "Net-(CON_SRC_IL-PadA)") (class "Default")
      (node (ref "CON_SRC_IL") (pin "A") (pinfunction "A_A") (pintype "passive"))
      (node (ref "R27") (pin "2") (pinfunction "2_2") (pintype "passive"))
    )
    (net (code "52") (name "Net-(CPC1002-Pad1)") (class "Default")
      (node (ref "CPC1002") (pin "1") (pinfunction "1_1") (pintype "passive"))
      (node (ref "R21") (pin "1") (pinfunction "1_1") (pintype "passive"))
    )
    (net (code "53") (name "Net-(D7-PadC)") (class "Default")
      (node (ref "D7") (pin "C") (pinfunction "C_C") (pintype "passive"))
      (node (ref "R46") (pin "2") (pinfunction "2_2") (pintype "passive"))
    )
    (net (code "54") (name "Net-(D8-PadA)") (class "Default")
      (node (ref "D8") (pin "A") (pinfunction "A_A") (pintype "passive"))
      (node (ref "R39") (pin "2") (pinfunction "2_2") (pintype "passive"))
    )
    (net (code "55") (name "Net-(ERROR_SIG-PadA)") (class "Default")
      (node (ref "ERROR_SIG") (pin "A") (pinfunction "A_A") (pintype "passive"))
      (node (ref "R30") (pin "2") (pinfunction "2_2") (pintype "passive"))
    )
    (net (code "56") (name "Net-(FUSE_1.5A-2)") (class "Default")
      (node (ref "FUSE_1.5A") (pin "P$2") (pinfunction "2_P$2") (pintype "passive"))
      (node (ref "SI4425") (pin "5") (pinfunction "D_1_5") (pintype "bidirectional"))
      (node (ref "SI4425") (pin "6") (pinfunction "D_2_6") (pintype "bidirectional"))
      (node (ref "SI4425") (pin "7") (pinfunction "D_3_7") (pintype "bidirectional"))
      (node (ref "SI4425") (pin "8") (pinfunction "D_4_8") (pintype "bidirectional"))
    )
    (net (code "57") (name "Net-(IC2E-VDD)") (class "Default")
      (node (ref "IC2") (pin "14") (pinfunction "VDD_14") (pintype "power_in"))
      (node (ref "R59") (pin "1") (pinfunction "1_1") (pintype "passive"))
    )
    (net (code "58") (name "Net-(IMD-PadA)") (class "Default")
      (node (ref "IMD") (pin "A") (pinfunction "A_A") (pintype "passive"))
      (node (ref "R15") (pin "1") (pinfunction "1_1") (pintype "passive"))
    )
    (net (code "59") (name "Net-(POWER-PadA)") (class "Default")
      (node (ref "POWER") (pin "A") (pinfunction "A_A") (pintype "passive"))
      (node (ref "R44") (pin "2") (pinfunction "2_2") (pintype "passive"))
    )
    (net (code "60") (name "Net-(R34-Pad2)") (class "Default")
      (node (ref "R34") (pin "2") (pinfunction "2_2") (pintype "passive"))
      (node (ref "TS_TRIG") (pin "A") (pinfunction "A_A") (pintype "passive"))
    )
    (net (code "61") (name "Net-(R54-Pad2)") (class "Default")
      (node (ref "R54") (pin "2") (pinfunction "2_2") (pintype "passive"))
      (node (ref "R56") (pin "1") (pinfunction "1_1") (pintype "passive"))
    )
    (net (code "62") (name "Net-(SI4425-S_1)") (class "Default")
      (node (ref "SI4425") (pin "1") (pinfunction "S_1_1") (pintype "bidirectional"))
      (node (ref "SI4425") (pin "2") (pinfunction "S_2_2") (pintype "bidirectional"))
      (node (ref "SI4425") (pin "3") (pinfunction "S_3_3") (pintype "bidirectional"))
      (node (ref "SUPPLY") (pin "2") (pinfunction "2_2") (pintype "passive"))
    )
    (net (code "63") (name "Net-(U$2A-+IN)") (class "Default")
      (node (ref "R32") (pin "2") (pinfunction "2_2") (pintype "passive"))
      (node (ref "U$2") (pin "3") (pinfunction "+IN_3") (pintype "input"))
    )
    (net (code "64") (name "Net-(U$2A--IN)") (class "Default")
      (node (ref "R33") (pin "2") (pinfunction "2_2") (pintype "passive"))
      (node (ref "U$2") (pin "2") (pinfunction "-IN_2") (pintype "input"))
    )
    (net (code "65") (name "Net-(U$2B-+IN)") (class "Default")
      (node (ref "R48") (pin "2") (pinfunction "2_2") (pintype "passive"))
      (node (ref "U$2") (pin "5") (pinfunction "+IN_5") (pintype "input"))
    )
    (net (code "66") (name "Net-(U$2B--IN)") (class "Default")
      (node (ref "R47") (pin "1") (pinfunction "1_1") (pintype "passive"))
      (node (ref "U$2") (pin "6") (pinfunction "-IN_6") (pintype "input"))
    )
    (net (code "67") (name "Net-(U$2C-V+)") (class "Default")
      (node (ref "R58") (pin "1") (pinfunction "1_1") (pintype "passive"))
      (node (ref "U$2") (pin "8") (pinfunction "V+_8") (pintype "power_in"))
    )
    (net (code "68") (name "Net-(U$4B--IN)") (class "Default")
      (node (ref "C16") (pin "1") (pinfunction "1_1") (pintype "passive"))
      (node (ref "R39") (pin "1") (pinfunction "1_1") (pintype "passive"))
      (node (ref "R46") (pin "1") (pinfunction "1_1") (pintype "passive"))
      (node (ref "U$4") (pin "6") (pinfunction "-IN_6") (pintype "input"))
    )
    (net (code "69") (name "Net-(U$4C-V+)") (class "Default")
      (node (ref "R57") (pin "1") (pinfunction "1_1") (pintype "passive"))
      (node (ref "U$4") (pin "8") (pinfunction "V+_8") (pintype "power_in"))
    )
    (net (code "70") (name "RISING_EDGE") (class "Default")
      (node (ref "IC2") (pin "5") (pinfunction "I0_5") (pintype "input"))
      (node (ref "RESET_TEST") (pin "3") (pinfunction "3_3") (pintype "passive"))
      (node (ref "U$2") (pin "7") (pinfunction "OUT_7") (pintype "output"))
    )
    (net (code "71") (name "SDC_COMP_POS") (class "Default")
      (node (ref "CHR_HDSCS") (pin "P$3") (pinfunction "3_P$3") (pintype "passive"))
      (node (ref "R3") (pin "1") (pinfunction "1_1") (pintype "passive"))
    )
    (net (code "72") (name "SDC_KILL") (class "Default")
      (node (ref "2V1") (pin "1") (pinfunction "1_1") (pintype "passive"))
      (node (ref "U$4") (pin "1") (pinfunction "OUT_1") (pintype "output"))
    )
    (net (code "73") (name "SHUTDOWN_FL") (class "Default")
      (node (ref "SDC-1") (pin "1") (pinfunction "S_1") (pintype "passive"))
      (node (ref "SDC-1") (pin "2") (pinfunction "S_2") (pintype "passive"))
      (node (ref "SDC-2") (pin "2") (pinfunction "S_2") (pintype "passive"))
    )
    (net (code "74") (name "SHUTDOWN_INTERLOCK_IN") (class "Default")
      (node (ref "SDC-2") (pin "1") (pinfunction "S_1") (pintype "passive"))
      (node (ref "SDC-3") (pin "1") (pinfunction "S_1") (pintype "passive"))
    )
    (net (code "75") (name "SP_RESET") (class "Default")
      (node (ref "CHR_HDP_1") (pin "P$7") (pinfunction "7_P$7") (pintype "passive"))
      (node (ref "JP3") (pin "1") (pinfunction "1_1") (pintype "passive"))
      (node (ref "R62") (pin "1") (pinfunction "1_1") (pintype "passive"))
      (node (ref "SP_RESET") (pin "TP") (pinfunction "TP_TP") (pintype "input"))
      (node (ref "SP_RESET2") (pin "TP") (pinfunction "TP_TP") (pintype "input"))
      (node (ref "U$11") (pin "1") (pinfunction "1_1") (pintype "bidirectional"))
      (node (ref "U$11") (pin "2") (pinfunction "2_2") (pintype "bidirectional"))
      (node (ref "U$11") (pin "5") (pinfunction "5_5") (pintype "bidirectional"))
      (node (ref "U$11") (pin "6") (pinfunction "6_6") (pintype "bidirectional"))
      (node (ref "U$11") (pin "D") (pinfunction "D0_D") (pintype "bidirectional"))
    )
    (net (code "76") (name "SP_RESET_INV") (class "Default")
      (node (ref "IC2") (pin "10") (pinfunction "O_10") (pintype "output"))
      (node (ref "R63") (pin "1") (pinfunction "1_1") (pintype "passive"))
      (node (ref "U$11") (pin "G") (pinfunction "G_G") (pintype "bidirectional"))
    )
    (net (code "77") (name "TO_GREEN_TSAL") (class "Default")
      (node (ref "CHR_HDP_1") (pin "P$1") (pinfunction "1_P$1") (pintype "passive"))
      (node (ref "CHR_HDSCS") (pin "P$2") (pinfunction "2_P$2") (pintype "passive"))
    )
    (net (code "78") (name "TO_RELAY") (class "Default")
      (node (ref "C15") (pin "1") (pinfunction "1_1") (pintype "passive"))
      (node (ref "D3") (pin "C") (pinfunction "C_C") (pintype "passive"))
      (node (ref "R25") (pin "2") (pinfunction "2_2") (pintype "passive"))
      (node (ref "U$3") (pin "1") (pinfunction "1_1") (pintype "bidirectional"))
      (node (ref "U$3") (pin "2") (pinfunction "2_2") (pintype "bidirectional"))
      (node (ref "U$3") (pin "5") (pinfunction "5_5") (pintype "bidirectional"))
      (node (ref "U$3") (pin "6") (pinfunction "6_6") (pintype "bidirectional"))
      (node (ref "U$3") (pin "D") (pinfunction "D0_D") (pintype "bidirectional"))
      (node (ref "U$9") (pin "P$1") (pinfunction "P1_P$1") (pintype "bidirectional"))
    )
    (net (code "79") (name "TO_SHUTDOWN") (class "Default")
      (node (ref "BYPASS-JP") (pin "1") (pinfunction "1_1") (pintype "passive"))
      (node (ref "C3") (pin "+") (pinfunction "+_+") (pintype "passive"))
      (node (ref "R49") (pin "2") (pinfunction "2_2") (pintype "passive"))
      (node (ref "SDC-3") (pin "2") (pinfunction "S_2") (pintype "passive"))
      (node (ref "U$9") (pin "P$4") (pinfunction "P4_P$4") (pintype "bidirectional"))
    )
    (net (code "80") (name "TS_TRIG") (class "Default")
      (node (ref "CPC1002") (pin "3") (pinfunction "3_3") (pintype "passive"))
      (node (ref "JP4") (pin "3") (pinfunction "3_3") (pintype "passive"))
      (node (ref "R34") (pin "1") (pinfunction "1_1") (pintype "passive"))
      (node (ref "TS-TRIG") (pin "TP") (pinfunction "TP_TP") (pintype "input"))
    )
    (net (code "81") (name "TS_TRIG1") (class "Default")
      (node (ref "555") (pin "2") (pinfunction "TR_2") (pintype "input"))
      (node (ref "JP4") (pin "2") (pinfunction "2_2") (pintype "passive"))
      (node (ref "R22") (pin "2") (pinfunction "2_2") (pintype "passive"))
    )
    (net (code "82") (name "VBUS_TEENSY") (class "Default")
      (node (ref "CHR_HDP_2") (pin "P$6") (pinfunction "6_P$6") (pintype "passive"))
      (node (ref "J2") (pin "1") (pinfunction "VBUS_1") (pintype "power_in"))
    )
    (net (code "83") (name "VREF-2V5") (class "Default")
      (node (ref "2V5") (pin "2") (pinfunction "2_2") (pintype "passive"))
      (node (ref "R45") (pin "1") (pinfunction "1_1") (pintype "passive"))
    )
    (net (code "84") (name "VREF-2V5-BF") (class "Default")
      (node (ref "2V5") (pin "1") (pinfunction "1_1") (pintype "passive"))
      (node (ref "U$1") (pin "6") (pinfunction "-IN_6") (pintype "input"))
      (node (ref "U$1") (pin "7") (pinfunction "OUT_7") (pintype "output"))
    )
    (net (code "85") (name "VREF-2V5-IN") (class "Default")
      (node (ref "2V5") (pin "3") (pinfunction "3_3") (pintype "passive"))
      (node (ref "R5") (pin "1") (pinfunction "1_1") (pintype "passive"))
      (node (ref "R6") (pin "2") (pinfunction "2_2") (pintype "passive"))
      (node (ref "U$1") (pin "5") (pinfunction "+IN_5") (pintype "input"))
    )
    (net (code "86") (name "VREF_8.5V") (class "Default")
      (node (ref "R2") (pin "S") (pinfunction "S_S") (pintype "passive"))
      (node (ref "U$4") (pin "2") (pinfunction "-IN_2") (pintype "input"))
    )
    (net (code "87") (name "unconnected-(CHRIN_STS_BRD-2-PadP$2)") (class "Default")
      (node (ref "CHRIN_STS_BRD") (pin "P$2") (pinfunction "2_P$2") (pintype "passive"))
    )
    (net (code "88") (name "unconnected-(CHR_HDP_2-1-PadP$1)") (class "Default")
      (node (ref "CHR_HDP_2") (pin "P$1") (pinfunction "1_P$1") (pintype "passive"))
    )
    (net (code "89") (name "unconnected-(IC2D-I0-Pad12)") (class "Default")
      (node (ref "IC2") (pin "12") (pinfunction "I0_12") (pintype "input"))
    )
    (net (code "90") (name "unconnected-(IC2D-I1-Pad13)") (class "Default")
      (node (ref "IC2") (pin "13") (pinfunction "I1_13") (pintype "input"))
    )
    (net (code "91") (name "unconnected-(IC2D-O-Pad11)") (class "Default")
      (node (ref "IC2") (pin "11") (pinfunction "O_11") (pintype "output"))
    )
  )
)
